# Power_Supply.net
KiCad netlist of a schematic drawn in Altium Designer
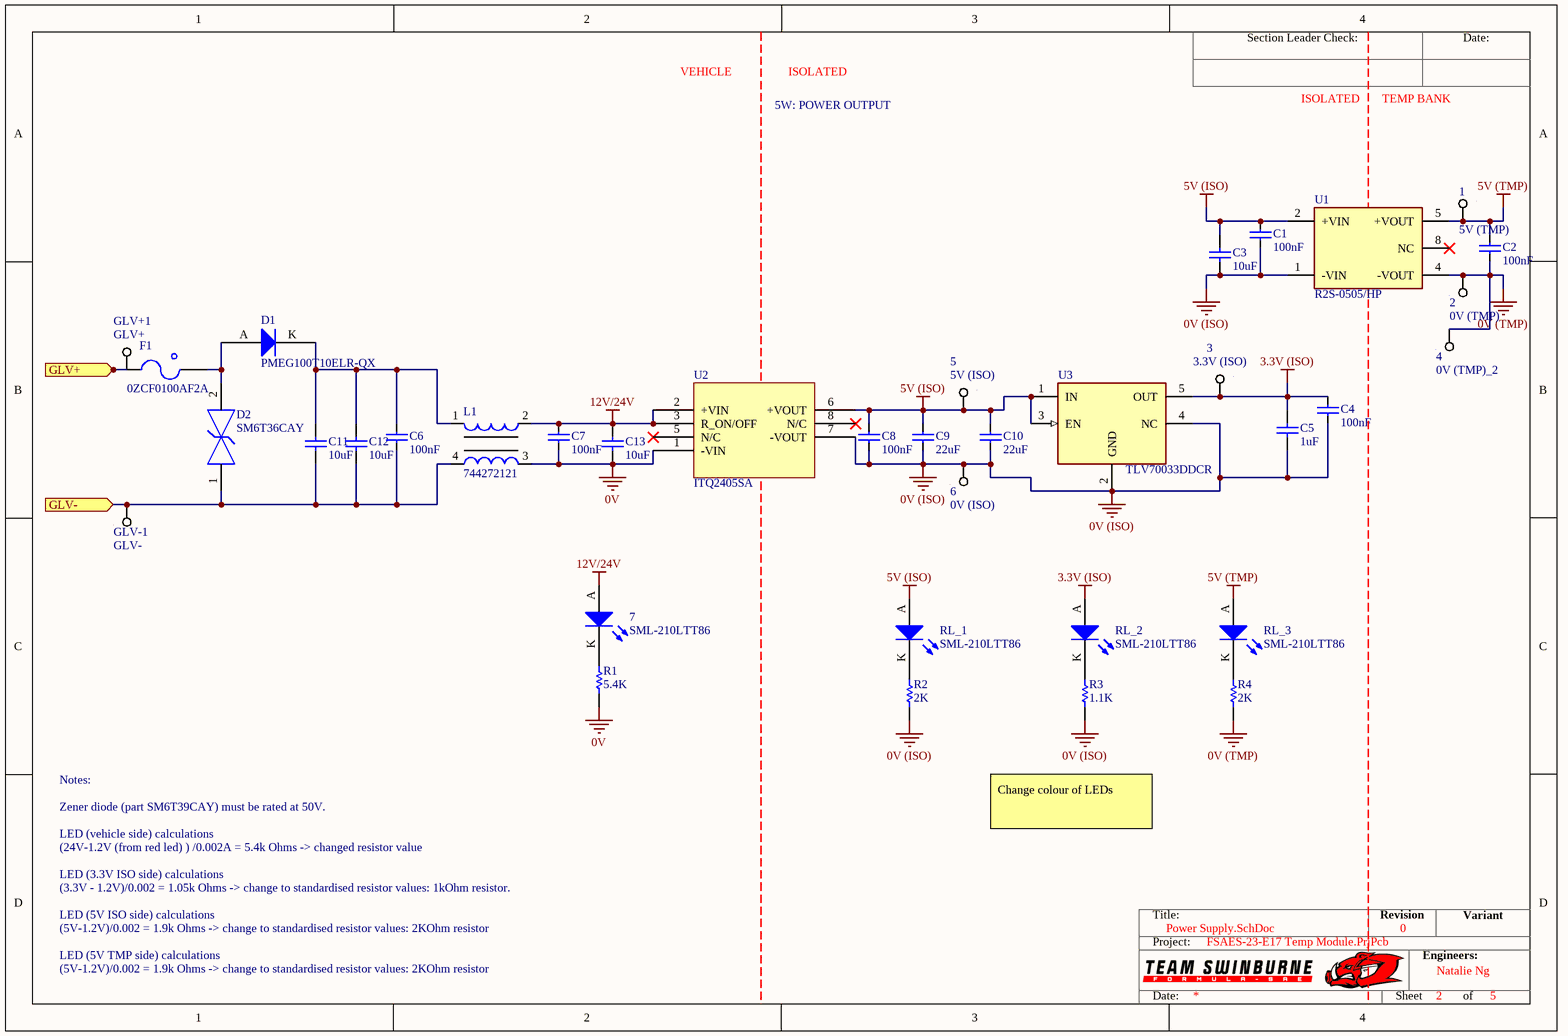
[diagram p0: Power Supply.SchDoc]

(export (version "E")
  (design (tool "Eeschema 10.0.6"))
  (components
    (comp (ref "1")
      (value "5V (TMP)")
      (footprint "SMD Test Point 1mm")
      (fields (field (name "PART NUMBER") "SMD Test Point Small") (field (name "CONTACT") "NA"))
      (libsource (lib "ts_20-standard-connectors") (part "Test Point Small"))
    )
    (comp (ref "2")
      (value "0V (TMP)")
      (footprint "SMD Test Point 1mm")
      (fields (field (name "PART NUMBER") "SMD Test Point Small") (field (name "CONTACT") "NA"))
      (libsource (lib "ts_20-standard-connectors") (part "Test Point Small"))
    )
    (comp (ref "3")
      (value "3.3V (ISO)")
      (footprint "SMD Test Point 1mm")
      (fields (field (name "PART NUMBER") "SMD Test Point Small") (field (name "CONTACT") "NA"))
      (libsource (lib "ts_20-standard-connectors") (part "Test Point Small"))
    )
    (comp (ref "4") (value "0V (TMP)_2") (libsource (lib "Team Swinburne") (part "Test Point Small")))
    (comp (ref "5")
      (value "5V (ISO)")
      (footprint "SMD Test Point 1mm")
      (fields (field (name "PART NUMBER") "SMD Test Point Small") (field (name "CONTACT") "NA"))
      (libsource (lib "ts_20-standard-connectors") (part "Test Point Small"))
    )
    (comp (ref "6")
      (value "0V (ISO)")
      (footprint "SMD Test Point 1mm")
      (fields (field (name "PART NUMBER") "SMD Test Point Small") (field (name "CONTACT") "NA"))
      (libsource (lib "ts_20-standard-connectors") (part "Test Point Small"))
    )
    (comp (ref "7")
      (value "SML-210LTT86")
      (footprint "0805 LED")
      (description "Red LED Indication - Discrete 1.75V 0805 (2012 Metric)")
      (libsource (lib "Team Swinburne") (part "LED"))
    )
    (comp (ref "C1")
      (value "100nF")
      (footprint "0805")
      (description "Cap Ceramic 0.1uF 25V X7R 10% Pad SMD 0805 125C Automotive T/R")
      (fields (field (name "TOLERANCE") "10%"))
      (libsource (lib "Team Swinburne") (part "Capacitors"))
    )
    (comp (ref "C2")
      (value "100nF")
      (footprint "0805")
      (description "Cap Ceramic 0.1uF 25V X7R 10% Pad SMD 0805 125C Automotive T/R")
      (fields (field (name "TOLERANCE") "10%"))
      (libsource (lib "Team Swinburne") (part "Capacitors"))
    )
    (comp (ref "C3")
      (value "10uF")
      (footprint "0805")
      (fields
        (field (name "PART NUMBER") "GRM21BR6YA106KE43L")
        (field (name "TOLERANCE") "10%")
        (field (name "MANUFACTURER") "muRata")
      )
      (libsource (lib "ts_20-standard-library") (part "Capacitor"))
    )
    (comp (ref "C4")
      (value "100nF")
      (footprint "0805")
      (description "Cap Ceramic 0.1uF 25V X7R 10% Pad SMD 0805 125C Automotive T/R")
      (fields (field (name "TOLERANCE") "10%"))
      (libsource (lib "Team Swinburne") (part "Capacitors"))
    )
    (comp (ref "C5")
      (value "1uF")
      (footprint "0805")
      (fields
        (field (name "PART NUMBER") "AC0805KKX7R8BB105")
        (field (name "TOLERANCE") "10%")
        (field (name "MANUFACTURER") "YAGEO")
      )
      (libsource (lib "ts_20-standard-library") (part "Capacitor"))
    )
    (comp (ref "C6")
      (value "100nF")
      (footprint "0805")
      (description "Cap Ceramic 0.1uF 25V X7R 10% Pad SMD 0805 125C Automotive T/R")
      (fields (field (name "TOLERANCE") "10%"))
      (libsource (lib "Team Swinburne") (part "Capacitors"))
    )
    (comp (ref "C7")
      (value "100nF")
      (footprint "0805")
      (description "Cap Ceramic 0.1uF 25V X7R 10% Pad SMD 0805 125C Automotive T/R")
      (fields (field (name "TOLERANCE") "10%"))
      (libsource (lib "Team Swinburne") (part "Capacitors"))
    )
    (comp (ref "C8")
      (value "100nF")
      (footprint "0805")
      (description "Cap Ceramic 0.1uF 25V X7R 10% Pad SMD 0805 125C Automotive T/R")
      (fields (field (name "TOLERANCE") "10%"))
      (libsource (lib "Team Swinburne") (part "Capacitors"))
    )
    (comp (ref "C9")
      (value "22uF")
      (footprint "C0805C226M9PAC7210-Footprint-1")
      (description "Cap Ceramic 22uF 6.3V X5R 20% Pad SMD 0805 85C T/R")
      (fields (field (name "TOLERANCE") "20%"))
      (libsource (lib "Team Swinburne") (part "C0805C226M9PAC7210-Symbol-1"))
    )
    (comp (ref "C10")
      (value "22uF")
      (footprint "C0805C226M9PAC7210-Footprint-1")
      (description "Cap Ceramic 22uF 6.3V X5R 20% Pad SMD 0805 85C T/R")
      (fields (field (name "TOLERANCE") "20%"))
      (libsource (lib "Team Swinburne") (part "C0805C226M9PAC7210-Symbol-1"))
    )
    (comp (ref "C11")
      (value "10uF")
      (footprint "CAPC2013X145X50NL20T25")
      (description "CAP CER 10UF 10V Y5V 0805")
      (fields (field (name "TOLERANCE") "80%"))
      (libsource (lib "Team Swinburne") (part "CAP-NP-2"))
    )
    (comp (ref "C12")
      (value "10uF")
      (footprint "CAPC2013X145X50NL20T25")
      (description "CAP CER 10UF 10V Y5V 0805")
      (fields (field (name "TOLERANCE") "80%"))
      (libsource (lib "Team Swinburne") (part "CAP-NP-2"))
    )
    (comp (ref "C13")
      (value "10uF")
      (footprint "CAPC2013X145X50NL20T25")
      (description "CAP CER 10UF 10V Y5V 0805")
      (fields (field (name "TOLERANCE") "80%"))
      (libsource (lib "Team Swinburne") (part "CAP-NP-2"))
    )
    (comp (ref "D1")
      (value "PMEG100T10ELR-QX")
      (footprint "SODFL350X110-2N")
      (description "Diode 100 V 1A Surface Mount SOD-123W")
      (libsource (lib "Team Swinburne") (part "PMEG100T10ELR-QX"))
    )
    (comp (ref "D2")
      (value "SM6T36CAY")
      (footprint "FP-SMB-CA-MFG")
      (description "ESD Suppressors / TVS Diodes 600 W 4kW Transil 6V to 70V Bi")
      (libsource (lib "Team Swinburne") (part "876f4347bf90aa6f500f43e3cd03972"))
    )
    (comp (ref "F1")
      (value "0ZCF0100AF2A")
      (footprint "2920")
      (description "PTC RESET FUSE 60V 1A 292")
      (libsource (lib "Team Swinburne") (part "PTC Fuse"))
    )
    (comp (ref "GLV+1")
      (value "GLV+")
      (footprint "SMD Test Point 1mm")
      (fields (field (name "PART NUMBER") "SMD Test Point Small") (field (name "CONTACT") "NA"))
      (libsource (lib "ts_20-standard-connectors") (part "Test Point Small"))
    )
    (comp (ref "GLV-1")
      (value "GLV-")
      (footprint "SMD Test Point 1mm")
      (fields (field (name "PART NUMBER") "SMD Test Point Small") (field (name "CONTACT") "NA"))
      (libsource (lib "ts_20-standard-connectors") (part "Test Point Small"))
    )
    (comp (ref "L1")
      (value "744272121")
      (footprint "WE-SL5")
      (description "CMC 120UH 2.5A 2LN 460 OHM SMD")
      (fields (field (name "TOLERANCE") "40%"))
      (libsource (lib "Team Swinburne") (part "PAS-IND-INDUCTOR-4A"))
    )
    (comp (ref "R1")
      (value "5.4K")
      (footprint "RNCF0805BKY5K40-Footprint-1")
      (description "RES SMD 5.4K OHM 0.125W 0805")
      (fields (field (name "TOLERANCE") "0.1%"))
      (libsource (lib "Team Swinburne") (part "RNCF0805BKY5K40-Symbol-1"))
    )
    (comp (ref "R2")
      (value "2K")
      (footprint "0805")
      (description "RC0805FR072KL")
      (fields (field (name "TOLERANCE") "0.01") (field (name "DIGIKEY PART NUMBER") "311-2.00KCRCT-ND"))
      (libsource (lib "Team Swinburne") (part "Resistor"))
    )
    (comp (ref "R3")
      (value "1.1K")
      (footprint "RESC0603")
      (description "RES SMD 1.1K OHM JUMPER 1/10W 0603")
      (fields (field (name "TOLERANCE") "1%"))
      (libsource (lib "Team Swinburne") (part "Resistor"))
    )
    (comp (ref "R4")
      (value "2K")
      (footprint "0805")
      (description "RC0805FR072KL")
      (fields (field (name "TOLERANCE") "0.01") (field (name "DIGIKEY PART NUMBER") "311-2.00KCRCT-ND"))
      (libsource (lib "Team Swinburne") (part "Resistor"))
    )
    (comp (ref "RL_1")
      (value "SML-210LTT86")
      (footprint "0805 LED")
      (description "Red LED Indication - Discrete 1.75V 0805 (2012 Metric)")
      (libsource (lib "Team Swinburne") (part "LED"))
    )
    (comp (ref "RL_2")
      (value "SML-210LTT86")
      (footprint "0805 LED")
      (description "Red LED Indication - Discrete 1.75V 0805 (2012 Metric)")
      (libsource (lib "Team Swinburne") (part "LED"))
    )
    (comp (ref "RL_3")
      (value "SML-210LTT86")
      (footprint "0805 LED")
      (description "Red LED Indication - Discrete 1.75V 0805 (2012 Metric)")
      (libsource (lib "Team Swinburne") (part "LED"))
    )
    (comp (ref "U1")
      (value "R2S-0505/HP")
      (footprint "R2S-0505_HP-Footprint-1")
      (description "DC-DC Unregulated Power Supply Module, 1 Output, 2W, Hybrid")
      (libsource (lib "Team Swinburne") (part "R2S-0505_HP-Symbol-1"))
    )
    (comp (ref "U2")
      (value "ITQ2405SA")
      (footprint "ITQ2405SA-Footprint-1")
      (description "Dc-dc Converter, 6W Single O/p, 4: 1 Input Sip")
      (libsource (lib "Team Swinburne") (part "ITQ2405SA-Symbol-1"))
    )
    (comp (ref "U3")
      (value "TLV70033DDCR")
      (footprint "FP-DDC0005A-IPC_B")
      (description "Fixed Positive LDO Regulator, 3.3V, 0.25V Dropout, PMOS, PDSO5")
      (libsource (lib "Team Swinburne") (part "c6f9311032385d92892323ecfb9e53c"))
    )
  )
  (nets
    (net (code "1") (name "/GLV+") (class "Default")
      (node (ref "F1") (pin "1") (pinfunction "1_1") (pintype "passive"))
      (node (ref "GLV+1") (pin "1") (pinfunction "1_1") (pintype "passive"))
    )
    (net (code "2") (name "/GLV-") (class "Default")
      (node (ref "C11") (pin "1") (pinfunction "1_1") (pintype "passive"))
      (node (ref "C12") (pin "1") (pinfunction "1_1") (pintype "passive"))
      (node (ref "C6") (pin "2") (pinfunction "2_2") (pintype "passive"))
      (node (ref "D2") (pin "1") (pinfunction "1_1") (pintype "passive"))
      (node (ref "GLV-1") (pin "1") (pinfunction "1_1") (pintype "passive"))
      (node (ref "L1") (pin "4") (pinfunction "4_4") (pintype "passive"))
    )
    (net (code "3") (name "0V") (class "Default")
      (node (ref "C13") (pin "1") (pinfunction "1_1") (pintype "passive"))
      (node (ref "C7") (pin "2") (pinfunction "2_2") (pintype "passive"))
      (node (ref "L1") (pin "3") (pinfunction "3_3") (pintype "passive"))
      (node (ref "R1") (pin "1") (pinfunction "1_1") (pintype "passive"))
      (node (ref "U2") (pin "1") (pinfunction "-VIN_1") (pintype "power_in"))
    )
    (net (code "4") (name "0V (ISO)") (class "Default")
      (node (ref "6") (pin "1") (pinfunction "1_1") (pintype "passive"))
      (node (ref "C1") (pin "2") (pinfunction "2_2") (pintype "passive"))
      (node (ref "C10") (pin "1") (pinfunction "1_1") (pintype "passive"))
      (node (ref "C3") (pin "1") (pinfunction "1_1") (pintype "passive"))
      (node (ref "C4") (pin "2") (pinfunction "2_2") (pintype "passive"))
      (node (ref "C5") (pin "1") (pinfunction "1_1") (pintype "passive"))
      (node (ref "C8") (pin "2") (pinfunction "2_2") (pintype "passive"))
      (node (ref "C9") (pin "1") (pinfunction "1_1") (pintype "passive"))
      (node (ref "R2") (pin "1") (pinfunction "1_1") (pintype "passive"))
      (node (ref "R3") (pin "1") (pinfunction "1_1") (pintype "passive"))
      (node (ref "U1") (pin "1") (pinfunction "-VIN_1") (pintype "power_in"))
      (node (ref "U2") (pin "7") (pinfunction "-VOUT_7") (pintype "power_in"))
      (node (ref "U3") (pin "2") (pinfunction "GND_2") (pintype "power_in"))
      (node (ref "U3") (pin "4") (pinfunction "NC_4") (pintype "passive"))
    )
    (net (code "5") (name "0V (TMP)") (class "Default")
      (node (ref "2") (pin "1") (pinfunction "1_1") (pintype "passive"))
      (node (ref "4") (pin "1") (pinfunction "1_1") (pintype "passive"))
      (node (ref "C2") (pin "2") (pinfunction "2_2") (pintype "passive"))
      (node (ref "R4") (pin "1") (pinfunction "1_1") (pintype "passive"))
      (node (ref "U1") (pin "4") (pinfunction "-VOUT_4") (pintype "power_in"))
    )
    (net (code "6") (name "3.3V (ISO)") (class "Default")
      (node (ref "3") (pin "1") (pinfunction "1_1") (pintype "passive"))
      (node (ref "C4") (pin "1") (pinfunction "1_1") (pintype "passive"))
      (node (ref "C5") (pin "2") (pinfunction "2_2") (pintype "passive"))
      (node (ref "RL_2") (pin "A") (pinfunction "A_A") (pintype "passive"))
      (node (ref "U3") (pin "5") (pinfunction "OUT_5") (pintype "power_in"))
    )
    (net (code "7") (name "5V (ISO)") (class "Default")
      (node (ref "5") (pin "1") (pinfunction "1_1") (pintype "passive"))
      (node (ref "C1") (pin "1") (pinfunction "1_1") (pintype "passive"))
      (node (ref "C10") (pin "2") (pinfunction "2_2") (pintype "passive"))
      (node (ref "C3") (pin "2") (pinfunction "2_2") (pintype "passive"))
      (node (ref "C8") (pin "1") (pinfunction "1_1") (pintype "passive"))
      (node (ref "C9") (pin "2") (pinfunction "2_2") (pintype "passive"))
      (node (ref "RL_1") (pin "A") (pinfunction "A_A") (pintype "passive"))
      (node (ref "U1") (pin "2") (pinfunction "+VIN_2") (pintype "power_in"))
      (node (ref "U2") (pin "6") (pinfunction "+VOUT_6") (pintype "power_in"))
      (node (ref "U3") (pin "1") (pinfunction "IN_1") (pintype "power_in"))
      (node (ref "U3") (pin "3") (pinfunction "EN_3") (pintype "input"))
    )
    (net (code "8") (name "5V (TMP)") (class "Default")
      (node (ref "1") (pin "1") (pinfunction "1_1") (pintype "passive"))
      (node (ref "C2") (pin "1") (pinfunction "1_1") (pintype "passive"))
      (node (ref "RL_3") (pin "A") (pinfunction "A_A") (pintype "passive"))
      (node (ref "U1") (pin "5") (pinfunction "+VOUT_5") (pintype "power_in"))
    )
    (net (code "9") (name "12V{slash}24V") (class "Default")
      (node (ref "7") (pin "A") (pinfunction "A_A") (pintype "passive"))
      (node (ref "C13") (pin "2") (pinfunction "2_2") (pintype "passive"))
      (node (ref "C7") (pin "1") (pinfunction "1_1") (pintype "passive"))
      (node (ref "L1") (pin "2") (pinfunction "2_2") (pintype "passive"))
      (node (ref "U2") (pin "2") (pinfunction "+VIN_2") (pintype "power_in"))
      (node (ref "U2") (pin "3") (pinfunction "R_ON/OFF_3") (pintype "power_in"))
    )
    (net (code "10") (name "Net-(7-PadK)") (class "Default")
      (node (ref "7") (pin "K") (pinfunction "K_K") (pintype "passive"))
      (node (ref "R1") (pin "2") (pinfunction "2_2") (pintype "passive"))
    )
    (net (code "11") (name "Net-(C11-Pad2)") (class "Default")
      (node (ref "C11") (pin "2") (pinfunction "2_2") (pintype "passive"))
      (node (ref "C12") (pin "2") (pinfunction "2_2") (pintype "passive"))
      (node (ref "C6") (pin "1") (pinfunction "1_1") (pintype "passive"))
      (node (ref "D1") (pin "K") (pintype "passive"))
      (node (ref "L1") (pin "1") (pinfunction "1_1") (pintype "passive"))
    )
    (net (code "12") (name "Net-(D1-PadA)") (class "Default")
      (node (ref "D1") (pin "A") (pintype "passive"))
      (node (ref "D2") (pin "2") (pinfunction "2_2") (pintype "passive"))
      (node (ref "F1") (pin "2") (pinfunction "2_2") (pintype "passive"))
    )
    (net (code "13") (name "Net-(R2-Pad2)") (class "Default")
      (node (ref "R2") (pin "2") (pinfunction "2_2") (pintype "passive"))
      (node (ref "RL_1") (pin "K") (pinfunction "K_K") (pintype "passive"))
    )
    (net (code "14") (name "Net-(R3-Pad2)") (class "Default")
      (node (ref "R3") (pin "2") (pinfunction "2_2") (pintype "passive"))
      (node (ref "RL_2") (pin "K") (pinfunction "K_K") (pintype "passive"))
    )
    (net (code "15") (name "Net-(R4-Pad2)") (class "Default")
      (node (ref "R4") (pin "2") (pinfunction "2_2") (pintype "passive"))
      (node (ref "RL_3") (pin "K") (pinfunction "K_K") (pintype "passive"))
    )
    (net (code "16") (name "unconnected-(U1-NC-Pad8)") (class "Default")
      (node (ref "U1") (pin "8") (pinfunction "NC_8") (pintype "passive+no_connect"))
    )
    (net (code "17") (name "unconnected-(U2-N{slash}C-Pad5)") (class "Default")
      (node (ref "U2") (pin "5") (pinfunction "N/C_5") (pintype "passive+no_connect"))
    )
    (net (code "18") (name "unconnected-(U2-N{slash}C-Pad8)") (class "Default")
      (node (ref "U2") (pin "8") (pinfunction "N/C_8") (pintype "passive+no_connect"))
    )
  )
)
